# SCH_Acid-Leak_2026-06-14.net
KiCad netlist of a schematic drawn in EasyEDA
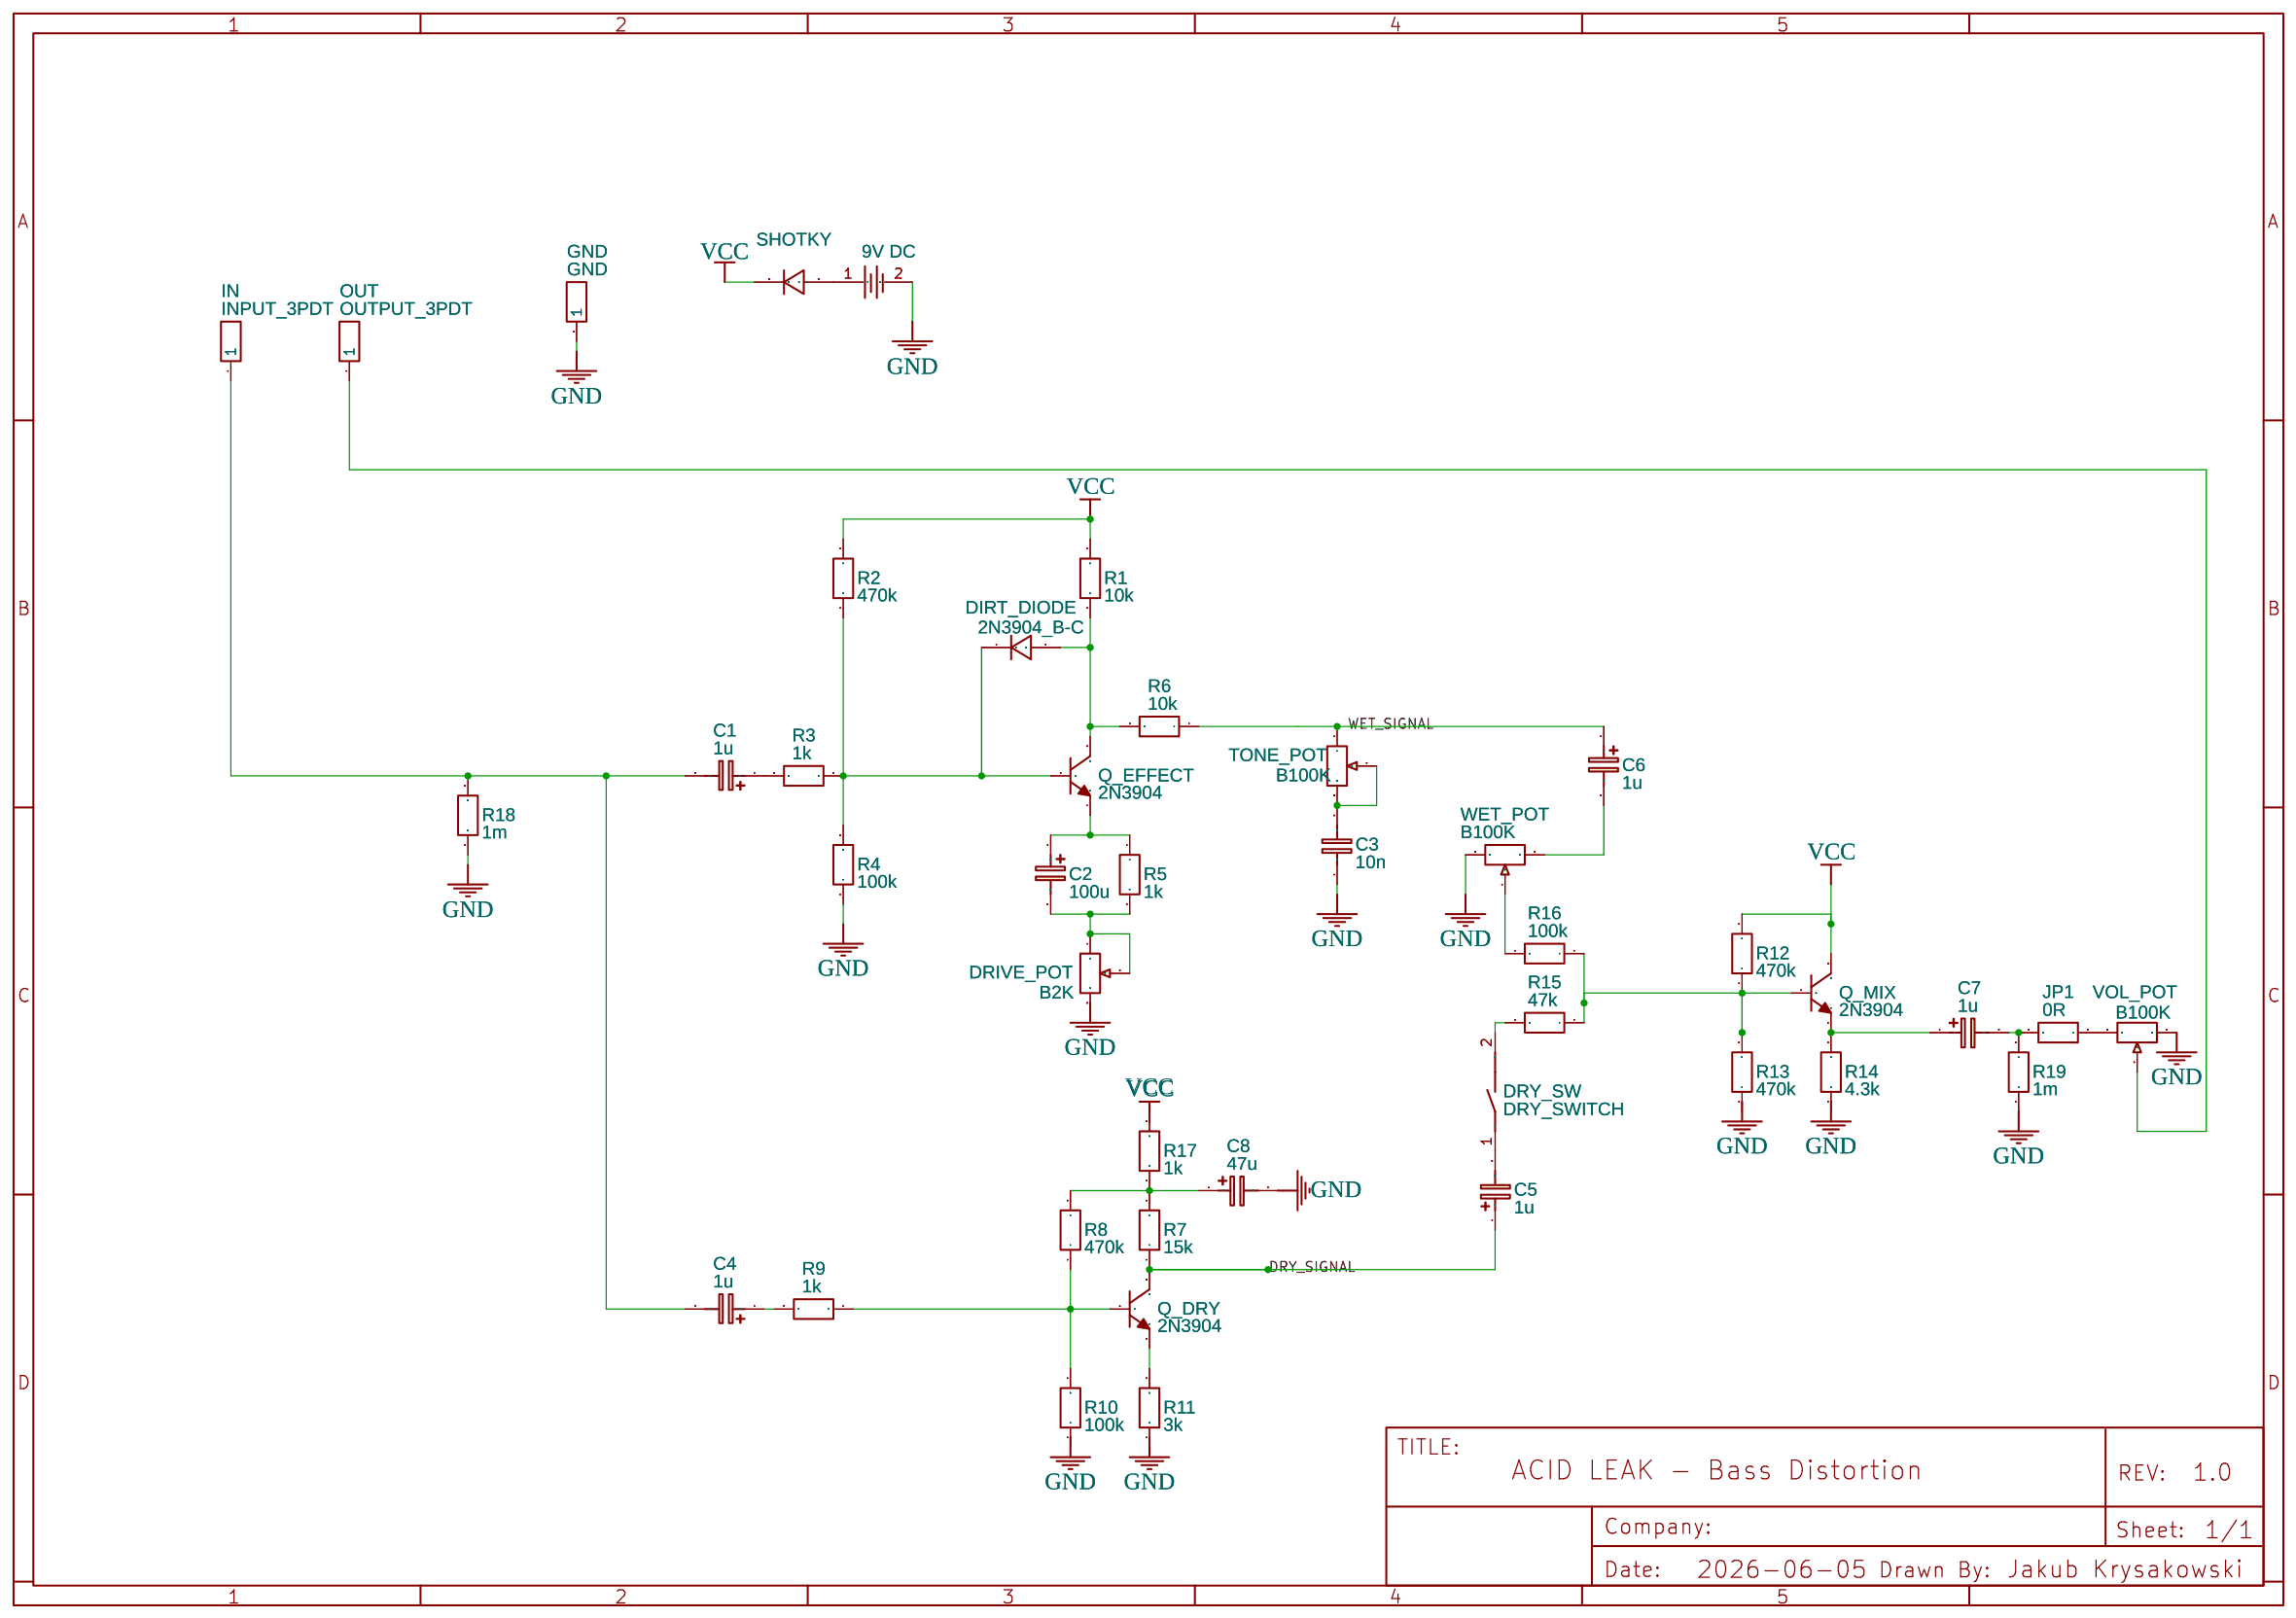
[diagram p0: schematic sheet]

(export (version "E")
  (design (tool "Eeschema 10.0.6"))
  (components
    (comp (ref "C1") (value "1u") (libsource (lib "") (part "CE_TH_D8.0×F3.5_EU_2")))
    (comp (ref "C2") (value "100u") (libsource (lib "") (part "CE_TH_D8.0×F3.5_EU_3")))
    (comp (ref "C3") (value "10n") (libsource (lib "") (part "C_RAD-0.1_EU")))
    (comp (ref "C4") (value "1u") (libsource (lib "") (part "CE_TH_D8.0×F3.5_EU")))
    (comp (ref "C5") (value "1u") (libsource (lib "") (part "CE_TH_D8.0×F3.5_EU_1")))
    (comp (ref "C6") (value "1u") (libsource (lib "") (part "CE_TH_D8.0×F3.5_EU_3")))
    (comp (ref "C7") (value "1u") (libsource (lib "") (part "CE_TH_D8.0×F3.5_EU_5")))
    (comp (ref "C8") (value "47u") (libsource (lib "") (part "CE_TH_D8.0×F3.5_EU_4")))
    (comp (ref "DIRT_DIODE")
      (value "2N3904_B-C")
      (fields (field (name "Manufacturer Part") "1N4148") (field (name "Manufacturer") "STMicroelectronics"))
      (libsource (lib "") (part "1N4148"))
    )
    (comp (ref "DRIVE_POT") (value "B2K") (libsource (lib "") (part "R_3296W_EU_1")))
    (comp (ref "DRY_SW")
      (value "DRY_SWITCH")
      (fields (field (name "Manufacturer Part") "DS-1-B-T") (field (name "Manufacturer") "XUNPU(讯普)"))
      (libsource (lib "") (part "DS-1-B-T"))
    )
    (comp (ref "GND") (value "GND") (libsource (lib "") (part "HDR-M-2.54_1x1_2")))
    (comp (ref "IN") (value "INPUT_3PDT") (libsource (lib "") (part "HDR-M-2.54_1x1")))
    (comp (ref "JP1") (value "0R") (libsource (lib "") (part "R_0603_EU_3")))
    (comp (ref "OUT") (value "OUTPUT_3PDT") (libsource (lib "") (part "HDR-M-2.54_1x1_1")))
    (comp (ref "PWR")
      (value "9V DC")
      (fields (field (name "Manufacturer Part") "BS-2-1") (field (name "Manufacturer") "Q&J"))
      (libsource (lib "") (part "CR2032-BS-2-1"))
    )
    (comp (ref "Q_DRY")
      (value "2N3904")
      (fields (field (name "Manufacturer Part") "2n3904S-RTK/PS") (field (name "Manufacturer") "KEC"))
      (libsource (lib "") (part "2N3904(SOT-23)"))
    )
    (comp (ref "Q_EFFECT")
      (value "2N3904")
      (fields (field (name "Manufacturer Part") "2n3904S-RTK/PS") (field (name "Manufacturer") "KEC"))
      (libsource (lib "") (part "2N3904(SOT-23)_2"))
    )
    (comp (ref "Q_MIX")
      (value "2N3904")
      (fields (field (name "Manufacturer Part") "2n3904S-RTK/PS") (field (name "Manufacturer") "KEC"))
      (libsource (lib "") (part "2N3904(SOT-23)_1"))
    )
    (comp (ref "R1") (value "10k") (libsource (lib "") (part "R_0603_EU")))
    (comp (ref "R2") (value "470k") (libsource (lib "") (part "R_0603_EU")))
    (comp (ref "R3") (value "1k") (libsource (lib "") (part "R_0603_EU_2")))
    (comp (ref "R4") (value "100k") (libsource (lib "") (part "R_0603_EU")))
    (comp (ref "R5") (value "1k") (libsource (lib "") (part "R_0603_EU_1")))
    (comp (ref "R6") (value "10k") (libsource (lib "") (part "R_0603_EU_2")))
    (comp (ref "R7") (value "15k") (libsource (lib "") (part "R_0603_EU")))
    (comp (ref "R8") (value "470k") (libsource (lib "") (part "R_0603_EU")))
    (comp (ref "R9") (value "1k") (libsource (lib "") (part "R_0603_EU_2")))
    (comp (ref "R10") (value "100k") (libsource (lib "") (part "R_0603_EU")))
    (comp (ref "R11") (value "3k") (libsource (lib "") (part "R_0603_EU")))
    (comp (ref "R12") (value "470k") (libsource (lib "") (part "R_0603_EU")))
    (comp (ref "R13") (value "470k") (libsource (lib "") (part "R_0603_EU")))
    (comp (ref "R14") (value "4.3k") (libsource (lib "") (part "R_0603_EU")))
    (comp (ref "R15") (value "47k") (libsource (lib "") (part "R_0603_EU_2")))
    (comp (ref "R16") (value "100k") (libsource (lib "") (part "R_0603_EU_2")))
    (comp (ref "R17") (value "1k") (libsource (lib "") (part "R_0603_EU")))
    (comp (ref "R18") (value "1m") (libsource (lib "") (part "R_0603_EU")))
    (comp (ref "R19") (value "1m") (libsource (lib "") (part "R_0603_EU")))
    (comp (ref "SHOTKY")
      (value "Shotky")
      (fields (field (name "Manufacturer Part") "1N4148") (field (name "Manufacturer") "STMicroelectronics"))
      (libsource (lib "") (part "1N4148_1"))
    )
    (comp (ref "TONE_POT") (value "B100K") (libsource (lib "") (part "R_3296W_EU_3")))
    (comp (ref "VOL_POT") (value "B100K") (libsource (lib "") (part "R_3296W_EU_2")))
    (comp (ref "WET_POT") (value "B100K") (libsource (lib "") (part "R_3296W_EU")))
  )
  (nets
    (net (code "1") (name "/DRY_SIGNAL") (class "Default")
      (node (ref "C5") (pin "1") (pinfunction "1_1") (pintype "unspecified"))
      (node (ref "Q_DRY") (pin "3") (pinfunction "C_3") (pintype "input"))
      (node (ref "R7") (pin "1") (pinfunction "1_1") (pintype "unspecified"))
    )
    (net (code "2") (name "/WET_SIGNAL") (class "Default")
      (node (ref "C6") (pin "1") (pinfunction "1_1") (pintype "unspecified"))
      (node (ref "R6") (pin "1") (pinfunction "1_1") (pintype "unspecified"))
      (node (ref "TONE_POT") (pin "1") (pinfunction "1_1") (pintype "input"))
    )
    (net (code "3") (name "GND") (class "Default")
      (node (ref "C3") (pin "1") (pinfunction "1_1") (pintype "unspecified"))
      (node (ref "C8") (pin "2") (pinfunction "2_2") (pintype "unspecified"))
      (node (ref "DRIVE_POT") (pin "3") (pinfunction "3_3") (pintype "input"))
      (node (ref "GND") (pin "1") (pinfunction "1_1") (pintype "input"))
      (node (ref "PWR") (pin "2") (pinfunction "2_2") (pintype "input"))
      (node (ref "R10") (pin "1") (pinfunction "1_1") (pintype "unspecified"))
      (node (ref "R11") (pin "1") (pinfunction "1_1") (pintype "unspecified"))
      (node (ref "R13") (pin "1") (pinfunction "1_1") (pintype "unspecified"))
      (node (ref "R14") (pin "1") (pinfunction "1_1") (pintype "unspecified"))
      (node (ref "R18") (pin "1") (pinfunction "1_1") (pintype "unspecified"))
      (node (ref "R19") (pin "1") (pinfunction "1_1") (pintype "unspecified"))
      (node (ref "R4") (pin "1") (pinfunction "1_1") (pintype "unspecified"))
      (node (ref "VOL_POT") (pin "1") (pinfunction "1_1") (pintype "input"))
      (node (ref "WET_POT") (pin "3") (pinfunction "3_3") (pintype "input"))
    )
    (net (code "4") (name "Net-(C1-Pad1)") (class "Default")
      (node (ref "C1") (pin "1") (pinfunction "1_1") (pintype "unspecified"))
      (node (ref "R3") (pin "2") (pinfunction "2_2") (pintype "unspecified"))
    )
    (net (code "5") (name "Net-(C1-Pad2)") (class "Default")
      (node (ref "C1") (pin "2") (pinfunction "2_2") (pintype "unspecified"))
      (node (ref "C4") (pin "2") (pinfunction "2_2") (pintype "unspecified"))
      (node (ref "IN") (pin "1") (pinfunction "1_1") (pintype "input"))
      (node (ref "R18") (pin "2") (pinfunction "2_2") (pintype "unspecified"))
    )
    (net (code "6") (name "Net-(C2-Pad2)") (class "Default")
      (node (ref "C2") (pin "2") (pinfunction "2_2") (pintype "unspecified"))
      (node (ref "DRIVE_POT") (pin "1") (pinfunction "1_1") (pintype "input"))
      (node (ref "DRIVE_POT") (pin "2") (pinfunction "2_2") (pintype "input"))
      (node (ref "R5") (pin "2") (pinfunction "2_2") (pintype "unspecified"))
    )
    (net (code "7") (name "Net-(C3-Pad2)") (class "Default")
      (node (ref "C3") (pin "2") (pinfunction "2_2") (pintype "unspecified"))
      (node (ref "TONE_POT") (pin "2") (pinfunction "2_2") (pintype "input"))
      (node (ref "TONE_POT") (pin "3") (pinfunction "3_3") (pintype "input"))
    )
    (net (code "8") (name "Net-(C4-Pad1)") (class "Default")
      (node (ref "C4") (pin "1") (pinfunction "1_1") (pintype "unspecified"))
      (node (ref "R9") (pin "2") (pinfunction "2_2") (pintype "unspecified"))
    )
    (net (code "9") (name "Net-(C5-Pad2)") (class "Default")
      (node (ref "C5") (pin "2") (pinfunction "2_2") (pintype "unspecified"))
      (node (ref "DRY_SW") (pin "1") (pinfunction "1_1") (pintype "unspecified"))
    )
    (net (code "10") (name "Net-(C6-Pad2)") (class "Default")
      (node (ref "C6") (pin "2") (pinfunction "2_2") (pintype "unspecified"))
      (node (ref "WET_POT") (pin "1") (pinfunction "1_1") (pintype "input"))
    )
    (net (code "11") (name "Net-(C7-Pad2)") (class "Default")
      (node (ref "C7") (pin "2") (pinfunction "2_2") (pintype "unspecified"))
      (node (ref "JP1") (pin "2") (pinfunction "2_2") (pintype "unspecified"))
      (node (ref "R19") (pin "2") (pinfunction "2_2") (pintype "unspecified"))
    )
    (net (code "12") (name "Net-(C8-Pad1)") (class "Default")
      (node (ref "C8") (pin "1") (pinfunction "1_1") (pintype "unspecified"))
      (node (ref "R17") (pin "1") (pinfunction "1_1") (pintype "unspecified"))
      (node (ref "R7") (pin "2") (pinfunction "2_2") (pintype "unspecified"))
      (node (ref "R8") (pin "2") (pinfunction "2_2") (pintype "unspecified"))
    )
    (net (code "13") (name "Net-(DRY_SW-Pad2)") (class "Default")
      (node (ref "DRY_SW") (pin "2") (pinfunction "2_2") (pintype "unspecified"))
      (node (ref "R15") (pin "2") (pinfunction "2_2") (pintype "unspecified"))
    )
    (net (code "14") (name "Net-(JP1-Pad1)") (class "Default")
      (node (ref "JP1") (pin "1") (pinfunction "1_1") (pintype "unspecified"))
      (node (ref "VOL_POT") (pin "3") (pinfunction "3_3") (pintype "input"))
    )
    (net (code "15") (name "Net-(OUT-Pad1)") (class "Default")
      (node (ref "OUT") (pin "1") (pinfunction "1_1") (pintype "input"))
      (node (ref "VOL_POT") (pin "2") (pinfunction "2_2") (pintype "input"))
    )
    (net (code "16") (name "Net-(PWR-Pad1)") (class "Default")
      (node (ref "PWR") (pin "1") (pinfunction "1_1") (pintype "input"))
      (node (ref "SHOTKY") (pin "2") (pinfunction "2_2") (pintype "unspecified"))
    )
    (net (code "17") (name "Net-(Q_DRY-B)") (class "Default")
      (node (ref "Q_DRY") (pin "2") (pinfunction "B_2") (pintype "input"))
      (node (ref "R10") (pin "2") (pinfunction "2_2") (pintype "unspecified"))
      (node (ref "R8") (pin "1") (pinfunction "1_1") (pintype "unspecified"))
      (node (ref "R9") (pin "1") (pinfunction "1_1") (pintype "unspecified"))
    )
    (net (code "18") (name "Net-(Q_DRY-E)") (class "Default")
      (node (ref "Q_DRY") (pin "1") (pinfunction "E_1") (pintype "input"))
      (node (ref "R11") (pin "2") (pinfunction "2_2") (pintype "unspecified"))
    )
    (net (code "19") (name "Net-(Q_EFFECT-B)") (class "Default")
      (node (ref "DIRT_DIODE") (pin "1") (pinfunction "1_1") (pintype "unspecified"))
      (node (ref "Q_EFFECT") (pin "2") (pinfunction "B_2") (pintype "input"))
      (node (ref "R2") (pin "1") (pinfunction "1_1") (pintype "unspecified"))
      (node (ref "R3") (pin "1") (pinfunction "1_1") (pintype "unspecified"))
      (node (ref "R4") (pin "2") (pinfunction "2_2") (pintype "unspecified"))
    )
    (net (code "20") (name "Net-(Q_EFFECT-C)") (class "Default")
      (node (ref "DIRT_DIODE") (pin "2") (pinfunction "2_2") (pintype "unspecified"))
      (node (ref "Q_EFFECT") (pin "3") (pinfunction "C_3") (pintype "input"))
      (node (ref "R1") (pin "1") (pinfunction "1_1") (pintype "unspecified"))
      (node (ref "R6") (pin "2") (pinfunction "2_2") (pintype "unspecified"))
    )
    (net (code "21") (name "Net-(Q_EFFECT-E)") (class "Default")
      (node (ref "C2") (pin "1") (pinfunction "1_1") (pintype "unspecified"))
      (node (ref "Q_EFFECT") (pin "1") (pinfunction "E_1") (pintype "input"))
      (node (ref "R5") (pin "1") (pinfunction "1_1") (pintype "unspecified"))
    )
    (net (code "22") (name "Net-(Q_MIX-B)") (class "Default")
      (node (ref "Q_MIX") (pin "2") (pinfunction "B_2") (pintype "input"))
      (node (ref "R12") (pin "1") (pinfunction "1_1") (pintype "unspecified"))
      (node (ref "R13") (pin "2") (pinfunction "2_2") (pintype "unspecified"))
      (node (ref "R15") (pin "1") (pinfunction "1_1") (pintype "unspecified"))
      (node (ref "R16") (pin "1") (pinfunction "1_1") (pintype "unspecified"))
    )
    (net (code "23") (name "Net-(Q_MIX-E)") (class "Default")
      (node (ref "C7") (pin "1") (pinfunction "1_1") (pintype "unspecified"))
      (node (ref "Q_MIX") (pin "1") (pinfunction "E_1") (pintype "input"))
      (node (ref "R14") (pin "2") (pinfunction "2_2") (pintype "unspecified"))
    )
    (net (code "24") (name "Net-(R16-Pad2)") (class "Default")
      (node (ref "R16") (pin "2") (pinfunction "2_2") (pintype "unspecified"))
      (node (ref "WET_POT") (pin "2") (pinfunction "2_2") (pintype "input"))
    )
    (net (code "25") (name "VCC") (class "Default")
      (node (ref "Q_MIX") (pin "3") (pinfunction "C_3") (pintype "input"))
      (node (ref "R1") (pin "2") (pinfunction "2_2") (pintype "unspecified"))
      (node (ref "R12") (pin "2") (pinfunction "2_2") (pintype "unspecified"))
      (node (ref "R17") (pin "2") (pinfunction "2_2") (pintype "unspecified"))
      (node (ref "R2") (pin "2") (pinfunction "2_2") (pintype "unspecified"))
      (node (ref "SHOTKY") (pin "1") (pinfunction "1_1") (pintype "unspecified"))
    )
  )
)
